# planespotter.net
KiCad netlist of a schematic drawn in Altium Designer
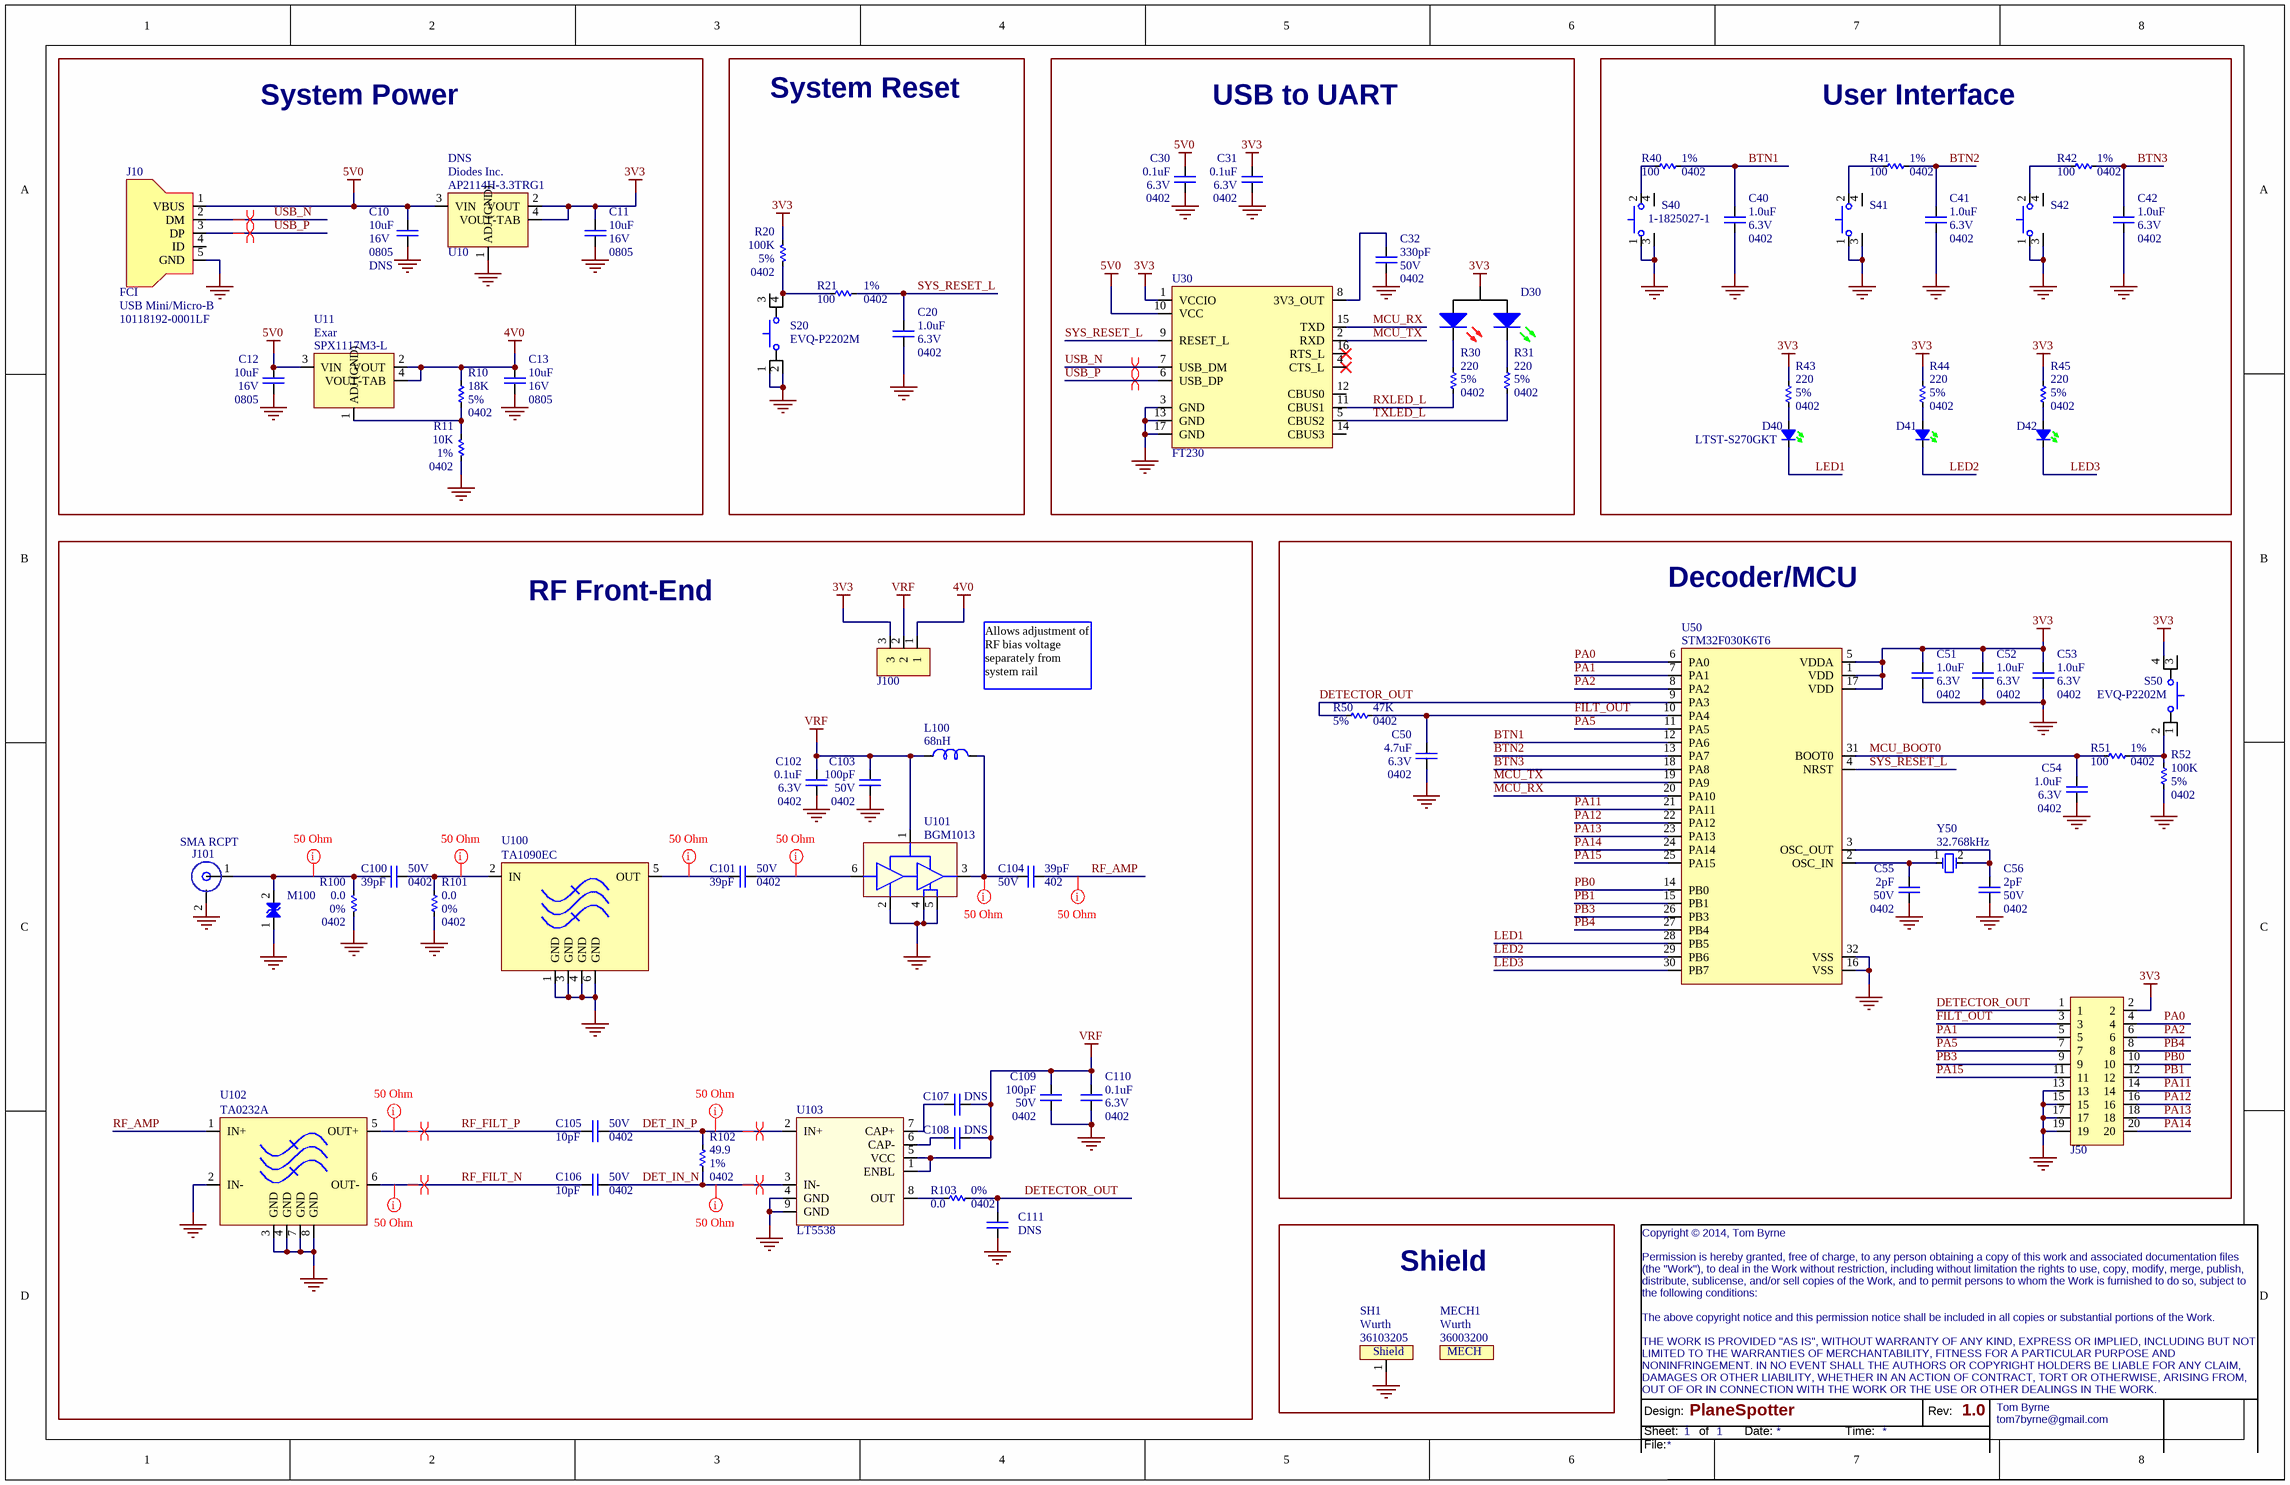
[diagram p0: planespotter.SchDoc]

(export (version "E")
  (design (tool "Eeschema 10.0.6"))
  (components
    (comp (ref "C10")
      (value "10uF")
      (footprint "CAPC2012X14N")
      (description "CAP,X5R,10uF,10%,16V,0805,#")
      (fields
        (field (name "TOLERANCE") "10%")
        (field (name "VOLTAGE") "16V")
        (field (name "PACKAGE") "0805")
        (field (name "PART NUMBER") "CAPC00037")
        (field (name "BOMOPTION") "DNS")
      )
      (libsource (lib "passives") (part "CAPC"))
    )
    (comp (ref "C11")
      (value "10uF")
      (footprint "CAPC2012X14N")
      (description "CAP,X5R,10uF,10%,16V,0805,#")
      (fields
        (field (name "TOLERANCE") "10%")
        (field (name "VOLTAGE") "16V")
        (field (name "PACKAGE") "0805")
        (field (name "PART NUMBER") "CAPC00037")
      )
      (libsource (lib "passives") (part "CAPC"))
    )
    (comp (ref "C12")
      (value "10uF")
      (footprint "CAPC2012X14N")
      (description "CAP,X5R,10uF,10%,16V,0805,#")
      (fields
        (field (name "TOLERANCE") "10%")
        (field (name "VOLTAGE") "16V")
        (field (name "PACKAGE") "0805")
        (field (name "PART NUMBER") "CAPC00037")
      )
      (libsource (lib "passives") (part "CAPC"))
    )
    (comp (ref "C13")
      (value "10uF")
      (footprint "CAPC2012X14N")
      (description "CAP,X5R,10uF,10%,16V,0805,#")
      (fields
        (field (name "TOLERANCE") "10%")
        (field (name "VOLTAGE") "16V")
        (field (name "PACKAGE") "0805")
        (field (name "PART NUMBER") "CAPC00037")
      )
      (libsource (lib "passives") (part "CAPC"))
    )
    (comp (ref "C20")
      (value "1.0uF")
      (footprint "CAPC1005X07N")
      (description "CAP,X5R,1.0uF,10%,6.3V, 0402,#")
      (fields
        (field (name "TOLERANCE") "10%")
        (field (name "VOLTAGE") "6.3V")
        (field (name "PACKAGE") "0402")
        (field (name "PART NUMBER") "CAPC00005")
      )
      (libsource (lib "passives") (part "CAPC"))
    )
    (comp (ref "C30")
      (value "0.1uF")
      (footprint "CAPC1005X07N")
      (description "CAP,X5R,0.1uF,10%,6.3V, 0402,#")
      (fields
        (field (name "TOLERANCE") "10%")
        (field (name "VOLTAGE") "6.3V")
        (field (name "PACKAGE") "0402")
        (field (name "PART NUMBER") "CAPC00002")
      )
      (libsource (lib "passives") (part "CAPC"))
    )
    (comp (ref "C31")
      (value "0.1uF")
      (footprint "CAPC1005X07N")
      (description "CAP,X5R,0.1uF,10%,6.3V, 0402,#")
      (fields
        (field (name "TOLERANCE") "10%")
        (field (name "VOLTAGE") "6.3V")
        (field (name "PACKAGE") "0402")
        (field (name "PART NUMBER") "CAPC00002")
      )
      (libsource (lib "passives") (part "CAPC"))
    )
    (comp (ref "C32")
      (value "330pF")
      (footprint "CAPC1005X07N")
      (description "CAP,C0G,330pF,5%,50V,0402")
      (fields
        (field (name "TOLERANCE") "5%")
        (field (name "VOLTAGE") "50V")
        (field (name "PACKAGE") "0402")
        (field (name "PART NUMBER") "CAPC00048")
      )
      (libsource (lib "passives") (part "CAPC"))
    )
    (comp (ref "C40")
      (value "1.0uF")
      (footprint "CAPC1005X07N")
      (description "CAP,X5R,1.0uF,10%,6.3V, 0402,#")
      (fields
        (field (name "TOLERANCE") "10%")
        (field (name "VOLTAGE") "6.3V")
        (field (name "PACKAGE") "0402")
        (field (name "PART NUMBER") "CAPC00005")
      )
      (libsource (lib "passives") (part "CAPC"))
    )
    (comp (ref "C41")
      (value "1.0uF")
      (footprint "CAPC1005X07N")
      (description "CAP,X5R,1.0uF,10%,6.3V, 0402,#")
      (fields
        (field (name "TOLERANCE") "10%")
        (field (name "VOLTAGE") "6.3V")
        (field (name "PACKAGE") "0402")
        (field (name "PART NUMBER") "CAPC00005")
      )
      (libsource (lib "passives") (part "CAPC"))
    )
    (comp (ref "C42")
      (value "1.0uF")
      (footprint "CAPC1005X07N")
      (description "CAP,X5R,1.0uF,10%,6.3V, 0402,#")
      (fields
        (field (name "TOLERANCE") "10%")
        (field (name "VOLTAGE") "6.3V")
        (field (name "PACKAGE") "0402")
        (field (name "PART NUMBER") "CAPC00005")
      )
      (libsource (lib "passives") (part "CAPC"))
    )
    (comp (ref "C50")
      (value "4.7uF")
      (footprint "CAPC1005X07N")
      (description "CAP,X5R,4.7uF,20%,6.3V, 0402")
      (fields
        (field (name "TOLERANCE") "20%")
        (field (name "VOLTAGE") "6.3V")
        (field (name "PACKAGE") "0402")
        (field (name "PART NUMBER") "CAPC00097")
      )
      (libsource (lib "passives") (part "CAPC"))
    )
    (comp (ref "C51")
      (value "1.0uF")
      (footprint "CAPC1005X07N")
      (description "CAP,X5R,1.0uF,10%,6.3V, 0402,#")
      (fields
        (field (name "TOLERANCE") "10%")
        (field (name "VOLTAGE") "6.3V")
        (field (name "PACKAGE") "0402")
        (field (name "PART NUMBER") "CAPC00005")
      )
      (libsource (lib "passives") (part "CAPC"))
    )
    (comp (ref "C52")
      (value "1.0uF")
      (footprint "CAPC1005X07N")
      (description "CAP,X5R,1.0uF,10%,6.3V, 0402,#")
      (fields
        (field (name "TOLERANCE") "10%")
        (field (name "VOLTAGE") "6.3V")
        (field (name "PACKAGE") "0402")
        (field (name "PART NUMBER") "CAPC00005")
      )
      (libsource (lib "passives") (part "CAPC"))
    )
    (comp (ref "C53")
      (value "1.0uF")
      (footprint "CAPC1005X07N")
      (description "CAP,X5R,1.0uF,10%,6.3V, 0402,#")
      (fields
        (field (name "TOLERANCE") "10%")
        (field (name "VOLTAGE") "6.3V")
        (field (name "PACKAGE") "0402")
        (field (name "PART NUMBER") "CAPC00005")
      )
      (libsource (lib "passives") (part "CAPC"))
    )
    (comp (ref "C54")
      (value "1.0uF")
      (footprint "CAPC1005X07N")
      (description "CAP,X5R,1.0uF,10%,6.3V, 0402,#")
      (fields
        (field (name "TOLERANCE") "10%")
        (field (name "VOLTAGE") "6.3V")
        (field (name "PACKAGE") "0402")
        (field (name "PART NUMBER") "CAPC00005")
      )
      (libsource (lib "passives") (part "CAPC"))
    )
    (comp (ref "C55")
      (value "2pF")
      (footprint "CAPC1005X07N")
      (description "CAP,C0G,2pF,±0.25pF,50V,0402")
      (fields
        (field (name "TOLERANCE") "0.25pF")
        (field (name "VOLTAGE") "50V")
        (field (name "PACKAGE") "0402")
        (field (name "PART NUMBER") "CAPC00100")
      )
      (libsource (lib "passives") (part "CAPC"))
    )
    (comp (ref "C56")
      (value "2pF")
      (footprint "CAPC1005X07N")
      (description "CAP,C0G,2pF,±0.25pF,50V,0402")
      (fields
        (field (name "TOLERANCE") "0.25pF")
        (field (name "VOLTAGE") "50V")
        (field (name "PACKAGE") "0402")
        (field (name "PART NUMBER") "CAPC00100")
      )
      (libsource (lib "passives") (part "CAPC"))
    )
    (comp (ref "C100")
      (value "39pF")
      (footprint "CAPC1005X07N")
      (description "CAP,39pF,50V,5%,NP0,0402")
      (fields
        (field (name "TOLERANCE") "5%")
        (field (name "VOLTAGE") "50V")
        (field (name "PACKAGE") "0402")
        (field (name "PART NUMBER") "CAP00012")
      )
      (libsource (lib "passives") (part "CAPC"))
    )
    (comp (ref "C101")
      (value "39pF")
      (footprint "CAPC1005X07N")
      (description "CAP,39pF,50V,5%,NP0,0402")
      (fields
        (field (name "TOLERANCE") "5%")
        (field (name "VOLTAGE") "50V")
        (field (name "PACKAGE") "0402")
        (field (name "PART NUMBER") "CAP00012")
      )
      (libsource (lib "passives") (part "CAPC"))
    )
    (comp (ref "C102")
      (value "0.1uF")
      (footprint "CAPC1005X07N")
      (description "CAP,X5R,0.1uF,10%,6.3V, 0402,#")
      (fields
        (field (name "TOLERANCE") "10%")
        (field (name "VOLTAGE") "6.3V")
        (field (name "PACKAGE") "0402")
        (field (name "PART NUMBER") "CAPC00002")
      )
      (libsource (lib "passives") (part "CAPC"))
    )
    (comp (ref "C103")
      (value "100pF")
      (footprint "CAPC1005X07N")
      (description "CAP,C0G,100pF,5%,50V,0402")
      (fields
        (field (name "TOLERANCE") "5%")
        (field (name "VOLTAGE") "50V")
        (field (name "PACKAGE") "0402")
        (field (name "PART NUMBER") "CAPC00043")
      )
      (libsource (lib "passives") (part "CAPC"))
    )
    (comp (ref "C104")
      (value "39pF")
      (footprint "CAPC1005X07N")
      (description "CAP,39pF,50V,5%,NP0,0402")
      (fields
        (field (name "TOLERANCE") "5%")
        (field (name "VOLTAGE") "50V")
        (field (name "PACKAGE") "402")
        (field (name "PART NUMBER") "CAP00012")
      )
      (libsource (lib "passives") (part "CAPC"))
    )
    (comp (ref "C105")
      (value "10pF")
      (footprint "CAPC1005X07N")
      (description "CAP,C0G,10pF,+/-0.25pF,50V, 0402")
      (fields
        (field (name "TOLERANCE") "0.25pF")
        (field (name "VOLTAGE") "50V")
        (field (name "PACKAGE") "0402")
        (field (name "PART NUMBER") "CAPC00008")
      )
      (libsource (lib "passives") (part "CAPC"))
    )
    (comp (ref "C106")
      (value "10pF")
      (footprint "CAPC1005X07N")
      (description "CAP,C0G,10pF,+/-0.25pF,50V, 0402")
      (fields
        (field (name "TOLERANCE") "0.25pF")
        (field (name "VOLTAGE") "50V")
        (field (name "PACKAGE") "0402")
        (field (name "PART NUMBER") "CAPC00008")
      )
      (libsource (lib "passives") (part "CAPC"))
    )
    (comp (ref "C107")
      (value "Ceramic Capacitor")
      (footprint "CAPC1005X07N")
      (description "CAP,X5R,0.1uF,10%,6.3V, 0402,#")
      (fields
        (field (name "TOLERANCE") "10%")
        (field (name "VOLTAGE") "6.3V")
        (field (name "BOMOPTION") "DNS")
      )
      (libsource (lib "passives") (part "CAPC"))
    )
    (comp (ref "C108")
      (value "Ceramic Capacitor")
      (footprint "CAPC1005X07N")
      (description "CAP,X5R,0.1uF,10%,6.3V, 0402,#")
      (fields
        (field (name "TOLERANCE") "10%")
        (field (name "VOLTAGE") "6.3V")
        (field (name "BOMOPTION") "DNS")
      )
      (libsource (lib "passives") (part "CAPC"))
    )
    (comp (ref "C109")
      (value "100pF")
      (footprint "CAPC1005X07N")
      (description "CAP,C0G,100pF,5%,50V,0402")
      (fields
        (field (name "TOLERANCE") "5%")
        (field (name "VOLTAGE") "50V")
        (field (name "PACKAGE") "0402")
        (field (name "PART NUMBER") "CAPC00043")
      )
      (libsource (lib "passives") (part "CAPC"))
    )
    (comp (ref "C110")
      (value "0.1uF")
      (footprint "CAPC1005X07N")
      (description "CAP,X5R,0.1uF,10%,6.3V, 0402,#")
      (fields
        (field (name "TOLERANCE") "10%")
        (field (name "VOLTAGE") "6.3V")
        (field (name "PACKAGE") "0402")
        (field (name "PART NUMBER") "CAPC00002")
      )
      (libsource (lib "passives") (part "CAPC"))
    )
    (comp (ref "C111")
      (value "Ceramic Capacitor")
      (footprint "CAPC1005X07N")
      (description "CAP,X5R,0.1uF,10%,6.3V, 0402,#")
      (fields
        (field (name "TOLERANCE") "10%")
        (field (name "VOLTAGE") "6.3V")
        (field (name "BOMOPTION") "DNS")
      )
      (libsource (lib "passives") (part "CAPC"))
    )
    (comp (ref "D30")
      (value "LED Red and Green")
      (footprint "XZMDKVG88W")
      (description "LED, Red and Green, Side-view, Common Anode, 1.95/2.1V, 630/570nm, 120/40mcd, SMT")
      (fields (field (name "PART NUMBER") "LED00009") (field (name "MANUFACTURER") "SunLED"))
      (libsource (lib "opto") (part "LED_REDGREEN_CA"))
    )
    (comp (ref "D40")
      (value "LED Green")
      (footprint "LED0603X3N-RA")
      (description "LED, Green, 2.1V, 569nm, 10mcd, 0603 Side-View")
      (fields
        (field (name "PART NUMBER") "LED00051")
        (field (name "MANUFACTURER") "Liteon")
        (field (name "MANUFACTURER PART NUMBER") "LTST-S270GKT")
      )
      (libsource (lib "opto") (part "LED_GRN"))
    )
    (comp (ref "D41")
      (value "LED Green")
      (footprint "LED0603X3N-RA")
      (description "LED, Green, 2.1V, 569nm, 10mcd, 0603 Side-View")
      (fields (field (name "PART NUMBER") "LED00051") (field (name "MANUFACTURER") "Liteon"))
      (libsource (lib "opto") (part "LED_GRN"))
    )
    (comp (ref "D42")
      (value "LED Green")
      (footprint "LED0603X3N-RA")
      (description "LED, Green, 2.1V, 569nm, 10mcd, 0603 Side-View")
      (fields (field (name "PART NUMBER") "LED00051") (field (name "MANUFACTURER") "Liteon"))
      (libsource (lib "opto") (part "LED_GRN"))
    )
    (comp (ref "J10")
      (value "USB Mini/Micro-B")
      (footprint "10118192-0001LF")
      (description "Conn, USB, RCPT, Type B, Micro, Surface Mount")
      (fields
        (field (name "PART NUMBER") "USB00005")
        (field (name "MANUFACTURER") "FCI")
        (field (name "MANUFACTURER PART NUMBER") "10118192-0001LF")
      )
      (libsource (lib "connectors") (part "USB_B_4M"))
    )
    (comp (ref "J50")
      (value "Header")
      (footprint "HDR254P2X10-N")
      (description "HDR, 2x10 Pin, 2.54mm Pitch, TH")
      (fields (field (name "PART NUMBER") "HDR00050") (field (name "MANUFACTURER") "FCI"))
      (libsource (lib "connectors") (part "HDR2X10"))
    )
    (comp (ref "J100")
      (value "Header")
      (footprint "HDR254P1X3-N")
      (description "HDR, 1x3 Pin, 2.54mm Pitch, Gold Flash, Vertical, TH")
      (fields (field (name "PART NUMBER") "HDR00003") (field (name "MANUFACTURER") "FCI"))
      (libsource (lib "connectors") (part "HDR1X3"))
    )
    (comp (ref "J101")
      (value "SMA RCPT")
      (footprint "142-0701-801")
      (description "CONN SMA JACK 50 OHM EDGE MNT")
      (fields (field (name "PART NUMBER") "CON00037") (field (name "MANUFACTURER") "Emerson NPC Johnson"))
      (libsource (lib "connectors") (part "RF_SMA_RCPT_BRD_EDGE"))
    )
    (comp (ref "L100")
      (value "68nH")
      (footprint "INDC1005X06N")
      (description "Chip Inductor, 68 nH, 180 mA, 1.2Ω, 0402")
      (fields (field (name "PART NUMBER") "IND00001") (field (name "TOLERANCE") "±5%"))
      (libsource (lib "passives") (part "INDUCTOR"))
    )
    (comp (ref "M100")
      (value "MOV")
      (footprint "VAR1005X06N")
      (description "Varistor,10V,10A,0402")
      (fields (field (name "PART NUMBER") "TVS00006") (field (name "MANUFACTURER") "Yageo"))
      (libsource (lib "discretes") (part "MOV"))
    )
    (comp (ref "MECH1")
      (value "Mechanical")
      (footprint "MECH")
      (description "RF Shield, Cover, 20mm x 20mm x 3mm")
      (fields
        (field (name "MANUFACTURER") "Wurth")
        (field (name "MANUFACTURER PART NUMBER") "36003200")
        (field (name "PART NUMBER") "SHD00002")
      )
      (libsource (lib "electromechanical") (part "MECH"))
    )
    (comp (ref "R10")
      (value "18K")
      (footprint "RESC1005X04N")
      (description "RES,18K,5%,0.063W,0402")
      (fields
        (field (name "PACKAGE") "0402")
        (field (name "TOLERANCE") "5%")
        (field (name "PART NUMBER") "RES00050")
        (field (name "POWER") "0.063W")
      )
      (libsource (lib "passives") (part "RES"))
    )
    (comp (ref "R11")
      (value "10K")
      (footprint "RESC1005X04N")
      (description "RES,10K,1%,0.063W,0402,#")
      (fields
        (field (name "PACKAGE") "0402")
        (field (name "TOLERANCE") "1%")
        (field (name "PART NUMBER") "RES00020")
        (field (name "POWER") "0.063W")
      )
      (libsource (lib "passives") (part "RES"))
    )
    (comp (ref "R20")
      (value "100K")
      (footprint "RESC1005X04N")
      (description "RES,100K,5%,0.063W,0402,#")
      (fields
        (field (name "PACKAGE") "0402")
        (field (name "TOLERANCE") "5%")
        (field (name "PART NUMBER") "RES00001")
        (field (name "POWER") "0.063W")
      )
      (libsource (lib "passives") (part "RES"))
    )
    (comp (ref "R21")
      (value "100")
      (footprint "RESC1005X04N")
      (description "RES,100 Ohm,1%,0.063W,0402,#")
      (fields
        (field (name "PACKAGE") "0402")
        (field (name "TOLERANCE") "1%")
        (field (name "PART NUMBER") "RES00024")
        (field (name "POWER") "0.063W")
      )
      (libsource (lib "passives") (part "RES"))
    )
    (comp (ref "R30")
      (value "220")
      (footprint "RESC1005X04N")
      (description "RES,220 Ohm,5%,0.063W,0402")
      (fields
        (field (name "PACKAGE") "0402")
        (field (name "TOLERANCE") "5%")
        (field (name "PART NUMBER") "RES00011")
        (field (name "POWER") "0.063W")
      )
      (libsource (lib "passives") (part "RES"))
    )
    (comp (ref "R31")
      (value "220")
      (footprint "RESC1005X04N")
      (description "RES,220 Ohm,5%,0.063W,0402")
      (fields
        (field (name "PACKAGE") "0402")
        (field (name "TOLERANCE") "5%")
        (field (name "PART NUMBER") "RES00011")
        (field (name "POWER") "0.063W")
      )
      (libsource (lib "passives") (part "RES"))
    )
    (comp (ref "R40")
      (value "100")
      (footprint "RESC1005X04N")
      (description "RES,100 Ohm,1%,0.063W,0402,#")
      (fields
        (field (name "PACKAGE") "0402")
        (field (name "TOLERANCE") "1%")
        (field (name "PART NUMBER") "RES00024")
        (field (name "POWER") "0.063W")
      )
      (libsource (lib "passives") (part "RES"))
    )
    (comp (ref "R41")
      (value "100")
      (footprint "RESC1005X04N")
      (description "RES,100 Ohm,1%,0.063W,0402,#")
      (fields
        (field (name "PACKAGE") "0402")
        (field (name "TOLERANCE") "1%")
        (field (name "PART NUMBER") "RES00024")
        (field (name "POWER") "0.063W")
      )
      (libsource (lib "passives") (part "RES"))
    )
    (comp (ref "R42")
      (value "100")
      (footprint "RESC1005X04N")
      (description "RES,100 Ohm,1%,0.063W,0402,#")
      (fields
        (field (name "PACKAGE") "0402")
        (field (name "TOLERANCE") "1%")
        (field (name "PART NUMBER") "RES00024")
        (field (name "POWER") "0.063W")
      )
      (libsource (lib "passives") (part "RES"))
    )
    (comp (ref "R43")
      (value "220")
      (footprint "RESC1005X04N")
      (description "RES,220 Ohm,5%,0.063W,0402")
      (fields
        (field (name "PACKAGE") "0402")
        (field (name "TOLERANCE") "5%")
        (field (name "PART NUMBER") "RES00011")
        (field (name "POWER") "0.063W")
      )
      (libsource (lib "passives") (part "RES"))
    )
    (comp (ref "R44")
      (value "220")
      (footprint "RESC1005X04N")
      (description "RES,220 Ohm,5%,0.063W,0402")
      (fields
        (field (name "PACKAGE") "0402")
        (field (name "TOLERANCE") "5%")
        (field (name "PART NUMBER") "RES00011")
        (field (name "POWER") "0.063W")
      )
      (libsource (lib "passives") (part "RES"))
    )
    (comp (ref "R45")
      (value "220")
      (footprint "RESC1005X04N")
      (description "RES,220 Ohm,5%,0.063W,0402")
      (fields
        (field (name "PACKAGE") "0402")
        (field (name "TOLERANCE") "5%")
        (field (name "PART NUMBER") "RES00011")
        (field (name "POWER") "0.063W")
      )
      (libsource (lib "passives") (part "RES"))
    )
    (comp (ref "R50")
      (value "47K")
      (footprint "RESC1005X04N")
      (description "RES,47K,5%,0.063W,0402")
      (fields
        (field (name "PACKAGE") "0402")
        (field (name "TOLERANCE") "5%")
        (field (name "PART NUMBER") "RES00008")
        (field (name "POWER") "0.063W")
      )
      (libsource (lib "passives") (part "RES"))
    )
    (comp (ref "R51")
      (value "100")
      (footprint "RESC1005X04N")
      (description "RES,100 Ohm,1%,0.063W,0402,#")
      (fields
        (field (name "PACKAGE") "0402")
        (field (name "TOLERANCE") "1%")
        (field (name "PART NUMBER") "RES00024")
        (field (name "POWER") "0.063W")
      )
      (libsource (lib "passives") (part "RES"))
    )
    (comp (ref "R52")
      (value "100K")
      (footprint "RESC1005X04N")
      (description "RES,100K,5%,0.063W,0402,#")
      (fields
        (field (name "PACKAGE") "0402")
        (field (name "TOLERANCE") "5%")
        (field (name "PART NUMBER") "RES00001")
        (field (name "POWER") "0.063W")
      )
      (libsource (lib "passives") (part "RES"))
    )
    (comp (ref "R100")
      (value "0.0")
      (footprint "RESC1005X04N")
      (description "RES,0 Ohm,0.063W,0402")
      (fields
        (field (name "PACKAGE") "0402")
        (field (name "TOLERANCE") "0%")
        (field (name "PART NUMBER") "RES00019")
        (field (name "POWER") "0.063W")
      )
      (libsource (lib "passives") (part "RES"))
    )
    (comp (ref "R101")
      (value "0.0")
      (footprint "RESC1005X04N")
      (description "RES,0 Ohm,0.063W,0402")
      (fields
        (field (name "PACKAGE") "0402")
        (field (name "TOLERANCE") "0%")
        (field (name "PART NUMBER") "RES00019")
        (field (name "POWER") "0.063W")
      )
      (libsource (lib "passives") (part "RES"))
    )
    (comp (ref "R102")
      (value "49.9")
      (footprint "RESC1005X04N")
      (description "RES,49.9 Ohm,1%,0.063W,0402")
      (fields
        (field (name "PACKAGE") "0402")
        (field (name "TOLERANCE") "1%")
        (field (name "PART NUMBER") "RES00104")
        (field (name "POWER") "0.1W")
      )
      (libsource (lib "passives") (part "RES"))
    )
    (comp (ref "R103")
      (value "0.0")
      (footprint "RESC1005X04N")
      (description "RES,0 Ohm,0.063W,0402")
      (fields
        (field (name "PACKAGE") "0402")
        (field (name "TOLERANCE") "0%")
        (field (name "PART NUMBER") "RES00019")
        (field (name "POWER") "0.063W")
      )
      (libsource (lib "passives") (part "RES"))
    )
    (comp (ref "S20")
      (value "Push Button")
      (footprint "BTN470X350X210-4N")
      (description "SPST- NO Momentary Button, 160g Force")
      (fields
        (field (name "PART NUMBER") "BTN00002")
        (field (name "MANUFACTURER") "Panasonic")
        (field (name "MANUFACTURER PART NUMBER") "EVQ-P2202M")
      )
      (libsource (lib "electromechanical") (part "BTN-4N"))
    )
    (comp (ref "S40")
      (value "Push Button")
      (footprint "1-1825027-1")
      (description "Button, SPST, Off-Momentary, Normally Open, 24V, 50mA, Round, 7mm")
      (fields
        (field (name "PART NUMBER") "BTN00002")
        (field (name "MANUFACTURER") "TE Connectivity")
        (field (name "MANUFACTURER PART NUMBER") "1-1825027-1")
      )
      (libsource (lib "electromechanical") (part "BTN-2N-2G"))
    )
    (comp (ref "S41")
      (value "Push Button")
      (footprint "1-1825027-1")
      (description "Button, SPST, Off-Momentary, Normally Open, 24V, 50mA, Round, 7mm")
      (fields (field (name "PART NUMBER") "BTN00002") (field (name "MANUFACTURER") "TE Connectivity"))
      (libsource (lib "electromechanical") (part "BTN-2N-2G"))
    )
    (comp (ref "S42")
      (value "Push Button")
      (footprint "1-1825027-1")
      (description "Button, SPST, Off-Momentary, Normally Open, 24V, 50mA, Round, 7mm")
      (fields (field (name "PART NUMBER") "BTN00002") (field (name "MANUFACTURER") "TE Connectivity"))
      (libsource (lib "electromechanical") (part "BTN-2N-2G"))
    )
    (comp (ref "S50")
      (value "Push Button")
      (footprint "BTN470X350X210-4N")
      (description "SPST- NO Momentary Button, 160g Force")
      (fields
        (field (name "PART NUMBER") "BTN00002")
        (field (name "MANUFACTURER") "Panasonic")
        (field (name "MANUFACTURER PART NUMBER") "EVQ-P2202M")
      )
      (libsource (lib "electromechanical") (part "BTN-4N"))
    )
    (comp (ref "SH1")
      (value "Sheild")
      (footprint "SHIELD_21x21x3_FRAME_SMD")
      (description "RF Shield, Frame, 20mm x 20mm x 3mm, SMD")
      (fields
        (field (name "MANUFACTURER") "Wurth")
        (field (name "MANUFACTURER PART NUMBER") "36103205")
        (field (name "PART NUMBER") "SHD00001")
      )
      (libsource (lib "electromechanical") (part "SHIELD-SMD"))
    )
    (comp (ref "U10")
      (value "AP1117")
      (footprint "SOT230P700X180-4N")
      (description "IC, LDO, Fixed 3.3V, 1A, 6VIN Max, Ceramic Stable, SOT-223")
      (fields
        (field (name "PART NUMBER") "IC00159")
        (field (name "MANUFACTURER") "Diodes Inc.")
        (field (name "MANUFACTURER PART NUMBER") "AP2114H-3.3TRG1")
        (field (name "BOMOPTION") "DNS")
      )
      (libsource (lib "ic") (part "AP1117"))
    )
    (comp (ref "U11")
      (value "AP1117")
      (footprint "SOT230P700X180-4N")
      (description "IC, LDO, Adjustable 2.6V-15V Out, 1.25V-15V In, 1A Max, Ceramic Stable, SOT-223")
      (fields
        (field (name "PART NUMBER") "IC00191")
        (field (name "MANUFACTURER") "Exar")
        (field (name "MANUFACTURER PART NUMBER") "SPX1117M3-L")
      )
      (libsource (lib "ic") (part "AP1117"))
    )
    (comp (ref "U30")
      (value "FT230")
      (footprint "QFN65P400X400X80_HS-17N")
      (description "USB Serial Translator, Basic, 16QFN")
      (fields (field (name "MANUFACTURER") "FTDI") (field (name "MANUFACTURER PART NUMBER") "FT230XQ-R"))
      (libsource (lib "ic") (part "FT230"))
    )
    (comp (ref "U50")
      (value "STM32F0")
      (footprint "TQFP80P900X900X160-32N")
      (description "MCU, ARM M0, 32K Flash, 32LQFP")
      (fields
        (field (name "MANUFACTURER") "STMicro")
        (field (name "MANUFACTURER PART NUMBER") "STM32F030K6T6")
        (field (name "PART NUMBER") "IC00001")
      )
      (libsource (lib "ic") (part "STM32F0"))
    )
    (comp (ref "U100")
      (value "TA1090EC")
      (footprint "QFN127P380X380X150-6N")
      (description "Filter, SAW, 1090 MHz, 30 MHz BW")
      (fields
        (field (name "MANUFACTURER") "Tai-Saw")
        (field (name "MANUFACTURER PART NUMBER") "TA1090EC")
        (field (name "PART NUMBER") "FILT00002")
      )
      (libsource (lib "rf") (part "TA1090EC"))
    )
    (comp (ref "U101")
      (value "BGM1013")
      (footprint "SOT65P210X80-6N")
      (description "RF Amplifier, 0-2.2GHz, 35.5dB, 6-TSSOP")
      (fields (field (name "MANUFACTURER") "NXP") (field (name "MANUFACTURER PART NUMBER") "BGM1013,115"))
      (libsource (lib "ic") (part "BGM1013"))
    )
    (comp (ref "U102")
      (value "TA0232A")
      (footprint "QFN127P380X380X125-8N")
      (description "Filter, SAW, 1090 MHz, 30 MHz BW")
      (fields (field (name "MANUFACTURER") "Tai-Saw") (field (name "PART NUMBER") "FILT00001"))
      (libsource (lib "rf") (part "TA0232A"))
    )
    (comp (ref "U103")
      (value "LT5538")
      (footprint "QFN50P300X300X80_HS-9N")
      (description "RF Log Power Detector, 40 MHz-3.8GHz, -75dBm - 10dBm, 3-5.25V, 8WFDFN")
      (fields
        (field (name "MANUFACTURER") "Linear")
        (field (name "MANUFACTURER PART NUMBER") "LT5538IDD#PBF")
      )
      (libsource (lib "ic") (part "LT5538"))
    )
    (comp (ref "Y50")
      (value "XTAL_COMPACT")
      (footprint "XTAL_32X15X09-2N")
      (description "XTAL, 32.768kHz, 20ppm, 6pF, 60K Ohm, 3215")
      (fields
        (field (name "MANUFACTURER") "Abracon")
        (field (name "MANUFACTURER PART NUMBER") "ABS07-120-32.768KHZ-T")
        (field (name "FREQUENCY") "32.768kHz")
      )
      (libsource (lib "xtalosc") (part "XTAL_COMPACT"))
    )
  )
  (nets
    (net (code "1") (name "/BTN1") (class "Default")
      (node (ref "C40") (pin "2") (pinfunction "2_2") (pintype "passive"))
      (node (ref "R40") (pin "2") (pinfunction "2_2") (pintype "passive"))
      (node (ref "U50") (pin "12") (pinfunction "PA6_12") (pintype "passive"))
    )
    (net (code "2") (name "/BTN2") (class "Default")
      (node (ref "C41") (pin "2") (pinfunction "2_2") (pintype "passive"))
      (node (ref "R41") (pin "2") (pinfunction "2_2") (pintype "passive"))
      (node (ref "U50") (pin "13") (pinfunction "PA7_13") (pintype "passive"))
    )
    (net (code "3") (name "/BTN3") (class "Default")
      (node (ref "C42") (pin "2") (pinfunction "2_2") (pintype "passive"))
      (node (ref "R42") (pin "2") (pinfunction "2_2") (pintype "passive"))
      (node (ref "U50") (pin "18") (pinfunction "PA8_18") (pintype "passive"))
    )
    (net (code "4") (name "/DETECTOR_OUT") (class "Default")
      (node (ref "C111") (pin "2") (pinfunction "2_2") (pintype "passive"))
      (node (ref "J50") (pin "1") (pinfunction "1_1") (pintype "passive"))
      (node (ref "R103") (pin "2") (pinfunction "2_2") (pintype "passive"))
      (node (ref "R50") (pin "1") (pinfunction "1_1") (pintype "passive"))
      (node (ref "U50") (pin "9") (pinfunction "PA3_9") (pintype "passive"))
    )
    (net (code "5") (name "/DET_IN_N") (class "Default")
      (node (ref "C106") (pin "1") (pinfunction "1_1") (pintype "passive"))
      (node (ref "R102") (pin "2") (pinfunction "2_2") (pintype "passive"))
      (node (ref "U103") (pin "3") (pinfunction "IN-_3") (pintype "passive"))
    )
    (net (code "6") (name "/DET_IN_P") (class "Default")
      (node (ref "C105") (pin "1") (pinfunction "1_1") (pintype "passive"))
      (node (ref "R102") (pin "1") (pinfunction "1_1") (pintype "passive"))
      (node (ref "U103") (pin "2") (pinfunction "IN+_2") (pintype "passive"))
    )
    (net (code "7") (name "/FILT_OUT") (class "Default")
      (node (ref "C50") (pin "2") (pinfunction "2_2") (pintype "passive"))
      (node (ref "J50") (pin "3") (pinfunction "3_3") (pintype "passive"))
      (node (ref "R50") (pin "2") (pinfunction "2_2") (pintype "passive"))
      (node (ref "U50") (pin "10") (pinfunction "PA4_10") (pintype "passive"))
    )
    (net (code "8") (name "/LED1") (class "Default")
      (node (ref "D40") (pin "K") (pinfunction "K_K") (pintype "passive"))
      (node (ref "U50") (pin "28") (pinfunction "PB5_28") (pintype "passive"))
    )
    (net (code "9") (name "/LED2") (class "Default")
      (node (ref "D41") (pin "K") (pinfunction "K_K") (pintype "passive"))
      (node (ref "U50") (pin "29") (pinfunction "PB6_29") (pintype "passive"))
    )
    (net (code "10") (name "/LED3") (class "Default")
      (node (ref "D42") (pin "K") (pinfunction "K_K") (pintype "passive"))
      (node (ref "U50") (pin "30") (pinfunction "PB7_30") (pintype "passive"))
    )
    (net (code "11") (name "/MCU_BOOT0") (class "Default")
      (node (ref "C54") (pin "2") (pinfunction "2_2") (pintype "passive"))
      (node (ref "R51") (pin "1") (pinfunction "1_1") (pintype "passive"))
      (node (ref "U50") (pin "31") (pinfunction "BOOT0_31") (pintype "passive"))
    )
    (net (code "12") (name "/MCU_RX") (class "Default")
      (node (ref "U30") (pin "15") (pinfunction "TXD_15") (pintype "passive"))
      (node (ref "U50") (pin "20") (pinfunction "PA10_20") (pintype "passive"))
    )
    (net (code "13") (name "/MCU_TX") (class "Default")
      (node (ref "U30") (pin "2") (pinfunction "RXD_2") (pintype "passive"))
      (node (ref "U50") (pin "19") (pinfunction "PA9_19") (pintype "passive"))
    )
    (net (code "14") (name "/PA0") (class "Default")
      (node (ref "J50") (pin "4") (pinfunction "4_4") (pintype "passive"))
      (node (ref "U50") (pin "6") (pinfunction "PA0_6") (pintype "passive"))
    )
    (net (code "15") (name "/PA1") (class "Default")
      (node (ref "J50") (pin "5") (pinfunction "5_5") (pintype "passive"))
      (node (ref "U50") (pin "7") (pinfunction "PA1_7") (pintype "passive"))
    )
    (net (code "16") (name "/PA2") (class "Default")
      (node (ref "J50") (pin "6") (pinfunction "6_6") (pintype "passive"))
      (node (ref "U50") (pin "8") (pinfunction "PA2_8") (pintype "passive"))
    )
    (net (code "17") (name "/PA5") (class "Default")
      (node (ref "J50") (pin "7") (pinfunction "7_7") (pintype "passive"))
      (node (ref "U50") (pin "11") (pinfunction "PA5_11") (pintype "passive"))
    )
    (net (code "18") (name "/PA11") (class "Default")
      (node (ref "J50") (pin "14") (pinfunction "14_14") (pintype "passive"))
      (node (ref "U50") (pin "21") (pinfunction "PA11_21") (pintype "passive"))
    )
    (net (code "19") (name "/PA12") (class "Default")
      (node (ref "J50") (pin "16") (pinfunction "16_16") (pintype "passive"))
      (node (ref "U50") (pin "22") (pinfunction "PA12_22") (pintype "passive"))
    )
    (net (code "20") (name "/PA13") (class "Default")
      (node (ref "J50") (pin "18") (pinfunction "18_18") (pintype "passive"))
      (node (ref "U50") (pin "23") (pinfunction "PA13_23") (pintype "passive"))
    )
    (net (code "21") (name "/PA14") (class "Default")
      (node (ref "J50") (pin "20") (pinfunction "20_20") (pintype "passive"))
      (node (ref "U50") (pin "24") (pinfunction "PA14_24") (pintype "passive"))
    )
    (net (code "22") (name "/PA15") (class "Default")
      (node (ref "J50") (pin "11") (pinfunction "11_11") (pintype "passive"))
      (node (ref "U50") (pin "25") (pinfunction "PA15_25") (pintype "passive"))
    )
    (net (code "23") (name "/PB0") (class "Default")
      (node (ref "J50") (pin "10") (pinfunction "10_10") (pintype "passive"))
      (node (ref "U50") (pin "14") (pinfunction "PB0_14") (pintype "passive"))
    )
    (net (code "24") (name "/PB1") (class "Default")
      (node (ref "J50") (pin "12") (pinfunction "12_12") (pintype "passive"))
      (node (ref "U50") (pin "15") (pinfunction "PB1_15") (pintype "passive"))
    )
    (net (code "25") (name "/PB3") (class "Default")
      (node (ref "J50") (pin "9") (pinfunction "9_9") (pintype "passive"))
      (node (ref "U50") (pin "26") (pinfunction "PB3_26") (pintype "passive"))
    )
    (net (code "26") (name "/PB4") (class "Default")
      (node (ref "J50") (pin "8") (pinfunction "8_8") (pintype "passive"))
      (node (ref "U50") (pin "27") (pinfunction "PB4_27") (pintype "passive"))
    )
    (net (code "27") (name "/RF_AMP") (class "Default")
      (node (ref "C104") (pin "1") (pinfunction "1_1") (pintype "passive"))
      (node (ref "U102") (pin "1") (pinfunction "IN+_1") (pintype "passive"))
    )
    (net (code "28") (name "/RF_FILT_N") (class "Default")
      (node (ref "C106") (pin "2") (pinfunction "2_2") (pintype "passive"))
      (node (ref "U102") (pin "6") (pinfunction "OUT-_6") (pintype "passive"))
    )
    (net (code "29") (name "/RF_FILT_P") (class "Default")
      (node (ref "C105") (pin "2") (pinfunction "2_2") (pintype "passive"))
      (node (ref "U102") (pin "5") (pinfunction "OUT+_5") (pintype "passive"))
    )
    (net (code "30") (name "/RXLED_L") (class "Default")
      (node (ref "R30") (pin "2") (pinfunction "2_2") (pintype "passive"))
      (node (ref "U30") (pin "11") (pinfunction "CBUS1_11") (pintype "passive"))
    )
    (net (code "31") (name "/SYS_RESET_L") (class "Default")
      (node (ref "C20") (pin "2") (pinfunction "2_2") (pintype "passive"))
      (node (ref "R21") (pin "2") (pinfunction "2_2") (pintype "passive"))
      (node (ref "U30") (pin "9") (pinfunction "RESET_L_9") (pintype "passive"))
      (node (ref "U50") (pin "4") (pinfunction "NRST_4") (pintype "passive"))
    )
    (net (code "32") (name "/TXLED_L") (class "Default")
      (node (ref "R31") (pin "2") (pinfunction "2_2") (pintype "passive"))
      (node (ref "U30") (pin "5") (pinfunction "CBUS2_5") (pintype "passive"))
    )
    (net (code "33") (name "/USB_N") (class "Default")
      (node (ref "J10") (pin "2") (pinfunction "DM_2") (pintype "passive"))
      (node (ref "U30") (pin "7") (pinfunction "USB_DM_7") (pintype "passive"))
    )
    (net (code "34") (name "/USB_P") (class "Default")
      (node (ref "J10") (pin "3") (pinfunction "DP_3") (pintype "passive"))
      (node (ref "U30") (pin "6") (pinfunction "USB_DP_6") (pintype "passive"))
    )
    (net (code "35") (name "3V3") (class "Default")
      (node (ref "C11") (pin "2") (pinfunction "2_2") (pintype "passive"))
      (node (ref "C31") (pin "2") (pinfunction "2_2") (pintype "passive"))
      (node (ref "C51") (pin "2") (pinfunction "2_2") (pintype "passive"))
      (node (ref "C52") (pin "2") (pinfunction "2_2") (pintype "passive"))
      (node (ref "C53") (pin "2") (pinfunction "2_2") (pintype "passive"))
      (node (ref "D30") (pin "A") (pinfunction "A_A") (pintype "passive"))
      (node (ref "J100") (pin "3") (pinfunction "3_3") (pintype "passive"))
      (node (ref "J50") (pin "2") (pinfunction "2_2") (pintype "passive"))
      (node (ref "R20") (pin "1") (pinfunction "1_1") (pintype "passive"))
      (node (ref "R43") (pin "1") (pinfunction "1_1") (pintype "passive"))
      (node (ref "R44") (pin "1") (pinfunction "1_1") (pintype "passive"))
      (node (ref "R45") (pin "1") (pinfunction "1_1") (pintype "passive"))
      (node (ref "S50") (pin "4") (pinfunction "4_4") (pintype "passive"))
      (node (ref "U10") (pin "2") (pinfunction "VOUT_2") (pintype "passive"))
      (node (ref "U10") (pin "4") (pinfunction "VOUT-TAB_4") (pintype "passive"))
      (node (ref "U30") (pin "1") (pinfunction "VCCIO_1") (pintype "passive"))
      (node (ref "U50") (pin "1") (pinfunction "VDD_1") (pintype "passive"))
      (node (ref "U50") (pin "17") (pinfunction "VDD_17") (pintype "passive"))
      (node (ref "U50") (pin "5") (pinfunction "VDDA_5") (pintype "passive"))
    )
    (net (code "36") (name "4V0") (class "Default")
      (node (ref "C13") (pin "2") (pinfunction "2_2") (pintype "passive"))
      (node (ref "J100") (pin "1") (pinfunction "1_1") (pintype "passive"))
      (node (ref "R10") (pin "1") (pinfunction "1_1") (pintype "passive"))
      (node (ref "U11") (pin "2") (pinfunction "VOUT_2") (pintype "passive"))
      (node (ref "U11") (pin "4") (pinfunction "VOUT-TAB_4") (pintype "passive"))
    )
    (net (code "37") (name "5V0") (class "Default")
      (node (ref "C10") (pin "2") (pinfunction "2_2") (pintype "passive"))
      (node (ref "C12") (pin "2") (pinfunction "2_2") (pintype "passive"))
      (node (ref "C30") (pin "2") (pinfunction "2_2") (pintype "passive"))
      (node (ref "J10") (pin "1") (pinfunction "VBUS_1") (pintype "passive"))
      (node (ref "U10") (pin "3") (pinfunction "VIN_3") (pintype "power_in"))
      (node (ref "U11") (pin "3") (pinfunction "VIN_3") (pintype "power_in"))
      (node (ref "U30") (pin "10") (pinfunction "VCC_10") (pintype "passive"))
    )
    (net (code "38") (name "GND") (class "Default")
      (node (ref "C10") (pin "1") (pinfunction "1_1") (pintype "passive"))
      (node (ref "C102") (pin "1") (pinfunction "1_1") (pintype "passive"))
      (node (ref "C103") (pin "1") (pinfunction "1_1") (pintype "passive"))
      (node (ref "C109") (pin "1") (pinfunction "1_1") (pintype "passive"))
      (node (ref "C11") (pin "1") (pinfunction "1_1") (pintype "passive"))
      (node (ref "C110") (pin "1") (pinfunction "1_1") (pintype "passive"))
      (node (ref "C111") (pin "1") (pinfunction "1_1") (pintype "passive"))
      (node (ref "C12") (pin "1") (pinfunction "1_1") (pintype "passive"))
      (node (ref "C13") (pin "1") (pinfunction "1_1") (pintype "passive"))
      (node (ref "C20") (pin "1") (pinfunction "1_1") (pintype "passive"))
      (node (ref "C30") (pin "1") (pinfunction "1_1") (pintype "passive"))
      (node (ref "C31") (pin "1") (pinfunction "1_1") (pintype "passive"))
      (node (ref "C32") (pin "1") (pinfunction "1_1") (pintype "passive"))
      (node (ref "C40") (pin "1") (pinfunction "1_1") (pintype "passive"))
      (node (ref "C41") (pin "1") (pinfunction "1_1") (pintype "passive"))
      (node (ref "C42") (pin "1") (pinfunction "1_1") (pintype "passive"))
      (node (ref "C50") (pin "1") (pinfunction "1_1") (pintype "passive"))
      (node (ref "C51") (pin "1") (pinfunction "1_1") (pintype "passive"))
      (node (ref "C52") (pin "1") (pinfunction "1_1") (pintype "passive"))
      (node (ref "C53") (pin "1") (pinfunction "1_1") (pintype "passive"))
      (node (ref "C54") (pin "1") (pinfunction "1_1") (pintype "passive"))
      (node (ref "C55") (pin "1") (pinfunction "1_1") (pintype "passive"))
      (node (ref "C56") (pin "1") (pinfunction "1_1") (pintype "passive"))
      (node (ref "J10") (pin "5") (pinfunction "GND_5") (pintype "passive"))
      (node (ref "J101") (pin "2") (pinfunction "GND_2") (pintype "passive"))
      (node (ref "J50") (pin "13") (pinfunction "13_13") (pintype "passive"))
      (node (ref "J50") (pin "15") (pinfunction "15_15") (pintype "passive"))
      (node (ref "J50") (pin "17") (pinfunction "17_17") (pintype "passive"))
      (node (ref "J50") (pin "19") (pinfunction "19_19") (pintype "passive"))
      (node (ref "M100") (pin "1") (pinfunction "A_1") (pintype "passive"))
      (node (ref "R100") (pin "2") (pinfunction "2_2") (pintype "passive"))
      (node (ref "R101") (pin "2") (pinfunction "2_2") (pintype "passive"))
      (node (ref "R11") (pin "2") (pinfunction "2_2") (pintype "passive"))
      (node (ref "R52") (pin "2") (pinfunction "2_2") (pintype "passive"))
      (node (ref "S20") (pin "1") (pinfunction "1_1") (pintype "passive"))
      (node (ref "S20") (pin "2") (pinfunction "2_2") (pintype "passive"))
      (node (ref "S40") (pin "1") (pinfunction "1_1") (pintype "passive"))
      (node (ref "S40") (pin "3") (pinfunction "3_3") (pintype "passive"))
      (node (ref "S41") (pin "1") (pinfunction "1_1") (pintype "passive"))
      (node (ref "S41") (pin "3") (pinfunction "3_3") (pintype "passive"))
      (node (ref "S42") (pin "1") (pinfunction "1_1") (pintype "passive"))
      (node (ref "S42") (pin "3") (pinfunction "3_3") (pintype "passive"))
      (node (ref "SH1") (pin "1") (pinfunction "1_1") (pintype "passive"))
      (node (ref "U10") (pin "1") (pinfunction "ADJ_(GND)_1") (pintype "power_in"))
      (node (ref "U100") (pin "1") (pinfunction "GND_1") (pintype "passive"))
      (node (ref "U100") (pin "3") (pinfunction "GND_3") (pintype "passive"))
      (node (ref "U100") (pin "4") (pinfunction "GND_4") (pintype "passive"))
      (node (ref "U100") (pin "6") (pinfunction "GND_6") (pintype "passive"))
      (node (ref "U101") (pin "2") (pinfunction "GND_2") (pintype "passive"))
      (node (ref "U101") (pin "4") (pinfunction "GND_4") (pintype "passive"))
      (node (ref "U101") (pin "5") (pinfunction "GND_5") (pintype "passive"))
      (node (ref "U102") (pin "2") (pinfunction "IN-_2") (pintype "passive"))
      (node (ref "U102") (pin "3") (pinfunction "GND_3") (pintype "passive"))
      (node (ref "U102") (pin "4") (pinfunction "GND_4") (pintype "passive"))
      (node (ref "U102") (pin "7") (pinfunction "GND_7") (pintype "passive"))
      (node (ref "U102") (pin "8") (pinfunction "GND_8") (pintype "passive"))
      (node (ref "U103") (pin "4") (pinfunction "GND_4") (pintype "passive"))
      (node (ref "U103") (pin "9") (pinfunction "GND_9") (pintype "passive"))
      (node (ref "U30") (pin "13") (pinfunction "GND_13") (pintype "passive"))
      (node (ref "U30") (pin "17") (pinfunction "GND_17") (pintype "passive"))
      (node (ref "U30") (pin "3") (pinfunction "GND_3") (pintype "passive"))
      (node (ref "U50") (pin "16") (pinfunction "VSS_16") (pintype "passive"))
      (node (ref "U50") (pin "32") (pinfunction "VSS_32") (pintype "passive"))
    )
    (net (code "39") (name "Net-(D30-PadKG)") (class "Default")
      (node (ref "D30") (pin "KG") (pinfunction "KG_KG") (pintype "passive"))
      (node (ref "R31") (pin "1") (pinfunction "1_1") (pintype "passive"))
    )
    (net (code "40") (name "Net-(D30-PadKR)") (class "Default")
      (node (ref "D30") (pin "KR") (pinfunction "KR_KR") (pintype "passive"))
      (node (ref "R30") (pin "1") (pinfunction "1_1") (pintype "passive"))
    )
    (net (code "41") (name "Net-(D40-PadA)") (class "Default")
      (node (ref "D40") (pin "A") (pinfunction "A_A") (pintype "passive"))
      (node (ref "R43") (pin "2") (pinfunction "2_2") (pintype "passive"))
    )
    (net (code "42") (name "Net-(D41-PadA)") (class "Default")
      (node (ref "D41") (pin "A") (pinfunction "A_A") (pintype "passive"))
      (node (ref "R44") (pin "2") (pinfunction "2_2") (pintype "passive"))
    )
    (net (code "43") (name "Net-(D42-PadA)") (class "Default")
      (node (ref "D42") (pin "A") (pinfunction "A_A") (pintype "passive"))
      (node (ref "R45") (pin "2") (pinfunction "2_2") (pintype "passive"))
    )
    (net (code "44") (name "Net-(J101-SHLD)") (class "Default")
      (node (ref "C100") (pin "2") (pinfunction "2_2") (pintype "passive"))
      (node (ref "J101") (pin "1") (pinfunction "SHLD_1") (pintype "power_in"))
      (node (ref "M100") (pin "2") (pinfunction "K_2") (pintype "passive"))
      (node (ref "R100") (pin "1") (pinfunction "1_1") (pintype "passive"))
    )
    (net (code "45") (name "Net-(R20-Pad2)") (class "Default")
      (node (ref "R20") (pin "2") (pinfunction "2_2") (pintype "passive"))
      (node (ref "R21") (pin "1") (pinfunction "1_1") (pintype "passive"))
      (node (ref "S20") (pin "4") (pinfunction "4_4") (pintype "passive"))
    )
    (net (code "46") (name "Net-(R40-Pad1)") (class "Default")
      (node (ref "R40") (pin "1") (pinfunction "1_1") (pintype "passive"))
      (node (ref "S40") (pin "2") (pinfunction "2_2") (pintype "passive"))
    )
    (net (code "47") (name "Net-(R41-Pad1)") (class "Default")
      (node (ref "R41") (pin "1") (pinfunction "1_1") (pintype "passive"))
      (node (ref "S41") (pin "2") (pinfunction "2_2") (pintype "passive"))
    )
    (net (code "48") (name "Net-(R42-Pad1)") (class "Default")
      (node (ref "R42") (pin "1") (pinfunction "1_1") (pintype "passive"))
      (node (ref "S42") (pin "2") (pinfunction "2_2") (pintype "passive"))
    )
    (net (code "49") (name "Net-(R51-Pad2)") (class "Default")
      (node (ref "R51") (pin "2") (pinfunction "2_2") (pintype "passive"))
      (node (ref "R52") (pin "1") (pinfunction "1_1") (pintype "passive"))
      (node (ref "S50") (pin "2") (pinfunction "2_2") (pintype "passive"))
    )
    (net (code "50") (name "Net-(U11-ADJ_(GND))") (class "Default")
      (node (ref "R10") (pin "2") (pinfunction "2_2") (pintype "passive"))
      (node (ref "R11") (pin "1") (pinfunction "1_1") (pintype "passive"))
      (node (ref "U11") (pin "1") (pinfunction "ADJ_(GND)_1") (pintype "power_in"))
    )
    (net (code "51") (name "Net-(U30-3V3_OUT)") (class "Default")
      (node (ref "C32") (pin "2") (pinfunction "2_2") (pintype "passive"))
      (node (ref "U30") (pin "8") (pinfunction "3V3_OUT_8") (pintype "passive"))
    )
    (net (code "52") (name "Net-(U50-OSC_IN)") (class "Default")
      (node (ref "C55") (pin "2") (pinfunction "2_2") (pintype "passive"))
      (node (ref "U50") (pin "2") (pinfunction "OSC_IN_2") (pintype "passive"))
      (node (ref "Y50") (pin "1") (pinfunction "OSC1_1") (pintype "passive"))
    )
    (net (code "53") (name "Net-(U50-OSC_OUT)") (class "Default")
      (node (ref "C56") (pin "2") (pinfunction "2_2") (pintype "passive"))
      (node (ref "U50") (pin "3") (pinfunction "OSC_OUT_3") (pintype "passive"))
      (node (ref "Y50") (pin "2") (pinfunction "OSC2_2") (pintype "passive"))
    )
    (net (code "54") (name "Net-(U100-IN)") (class "Default")
      (node (ref "C100") (pin "1") (pinfunction "1_1") (pintype "passive"))
      (node (ref "R101") (pin "1") (pinfunction "1_1") (pintype "passive"))
      (node (ref "U100") (pin "2") (pinfunction "IN_2") (pintype "passive"))
    )
    (net (code "55") (name "Net-(U100-OUT)") (class "Default")
      (node (ref "C101") (pin "2") (pinfunction "2_2") (pintype "passive"))
      (node (ref "U100") (pin "5") (pinfunction "OUT_5") (pintype "passive"))
    )
    (net (code "56") (name "Net-(U101-RF_IN)") (class "Default")
      (node (ref "C101") (pin "1") (pinfunction "1_1") (pintype "passive"))
      (node (ref "U101") (pin "6") (pinfunction "RF_IN_6") (pintype "passive"))
    )
    (net (code "57") (name "Net-(U101-RF_OUT)") (class "Default")
      (node (ref "C104") (pin "2") (pinfunction "2_2") (pintype "passive"))
      (node (ref "L100") (pin "2") (pinfunction "2_2") (pintype "passive"))
      (node (ref "U101") (pin "3") (pinfunction "RF_OUT_3") (pintype "passive"))
    )
    (net (code "58") (name "Net-(U103-CAP+)") (class "Default")
      (node (ref "C107") (pin "1") (pinfunction "1_1") (pintype "passive"))
      (node (ref "U103") (pin "7") (pinfunction "CAP+_7") (pintype "passive"))
    )
    (net (code "59") (name "Net-(U103-CAP-)") (class "Default")
      (node (ref "C108") (pin "2") (pinfunction "2_2") (pintype "passive"))
      (node (ref "U103") (pin "6") (pinfunction "CAP-_6") (pintype "passive"))
    )
    (net (code "60") (name "Net-(U103-OUT)") (class "Default")
      (node (ref "R103") (pin "1") (pinfunction "1_1") (pintype "passive"))
      (node (ref "U103") (pin "8") (pinfunction "OUT_8") (pintype "passive"))
    )
    (net (code "61") (name "VRF") (class "Default")
      (node (ref "C102") (pin "2") (pinfunction "2_2") (pintype "passive"))
      (node (ref "C103") (pin "2") (pinfunction "2_2") (pintype "passive"))
      (node (ref "C107") (pin "2") (pinfunction "2_2") (pintype "passive"))
      (node (ref "C108") (pin "1") (pinfunction "1_1") (pintype "passive"))
      (node (ref "C109") (pin "2") (pinfunction "2_2") (pintype "passive"))
      (node (ref "C110") (pin "2") (pinfunction "2_2") (pintype "passive"))
      (node (ref "J100") (pin "2") (pinfunction "2_2") (pintype "passive"))
      (node (ref "L100") (pin "1") (pinfunction "1_1") (pintype "passive"))
      (node (ref "U101") (pin "1") (pinfunction "VDD_1") (pintype "passive"))
      (node (ref "U103") (pin "1") (pinfunction "ENBL_1") (pintype "passive"))
      (node (ref "U103") (pin "5") (pinfunction "VCC_5") (pintype "passive"))
    )
    (net (code "62") (name "unconnected-(J10-ID-Pad4)") (class "Default")
      (node (ref "J10") (pin "4") (pinfunction "ID_4") (pintype "passive"))
    )
    (net (code "63") (name "unconnected-(S20-Pad3)") (class "Default")
      (node (ref "S20") (pin "3") (pinfunction "3_3") (pintype "passive"))
    )
    (net (code "64") (name "unconnected-(S40-Pad4)") (class "Default")
      (node (ref "S40") (pin "4") (pinfunction "4_4") (pintype "passive"))
    )
    (net (code "65") (name "unconnected-(S41-Pad4)") (class "Default")
      (node (ref "S41") (pin "4") (pinfunction "4_4") (pintype "passive"))
    )
    (net (code "66") (name "unconnected-(S42-Pad4)") (class "Default")
      (node (ref "S42") (pin "4") (pinfunction "4_4") (pintype "passive"))
    )
    (net (code "67") (name "unconnected-(S50-Pad1)") (class "Default")
      (node (ref "S50") (pin "1") (pinfunction "1_1") (pintype "passive"))
    )
    (net (code "68") (name "unconnected-(S50-Pad3)") (class "Default")
      (node (ref "S50") (pin "3") (pinfunction "3_3") (pintype "passive"))
    )
    (net (code "69") (name "unconnected-(U30-CBUS0-Pad12)") (class "Default")
      (node (ref "U30") (pin "12") (pinfunction "CBUS0_12") (pintype "passive"))
    )
    (net (code "70") (name "unconnected-(U30-CBUS3-Pad14)") (class "Default")
      (node (ref "U30") (pin "14") (pinfunction "CBUS3_14") (pintype "passive"))
    )
    (net (code "71") (name "unconnected-(U30-CTS_L-Pad4)") (class "Default")
      (node (ref "U30") (pin "4") (pinfunction "CTS_L_4") (pintype "passive+no_connect"))
    )
    (net (code "72") (name "unconnected-(U30-RTS_L-Pad16)") (class "Default")
      (node (ref "U30") (pin "16") (pinfunction "RTS_L_16") (pintype "passive+no_connect"))
    )
  )
)
